# GPIOPins.net
KiCad netlist of a schematic drawn in Altium Designer
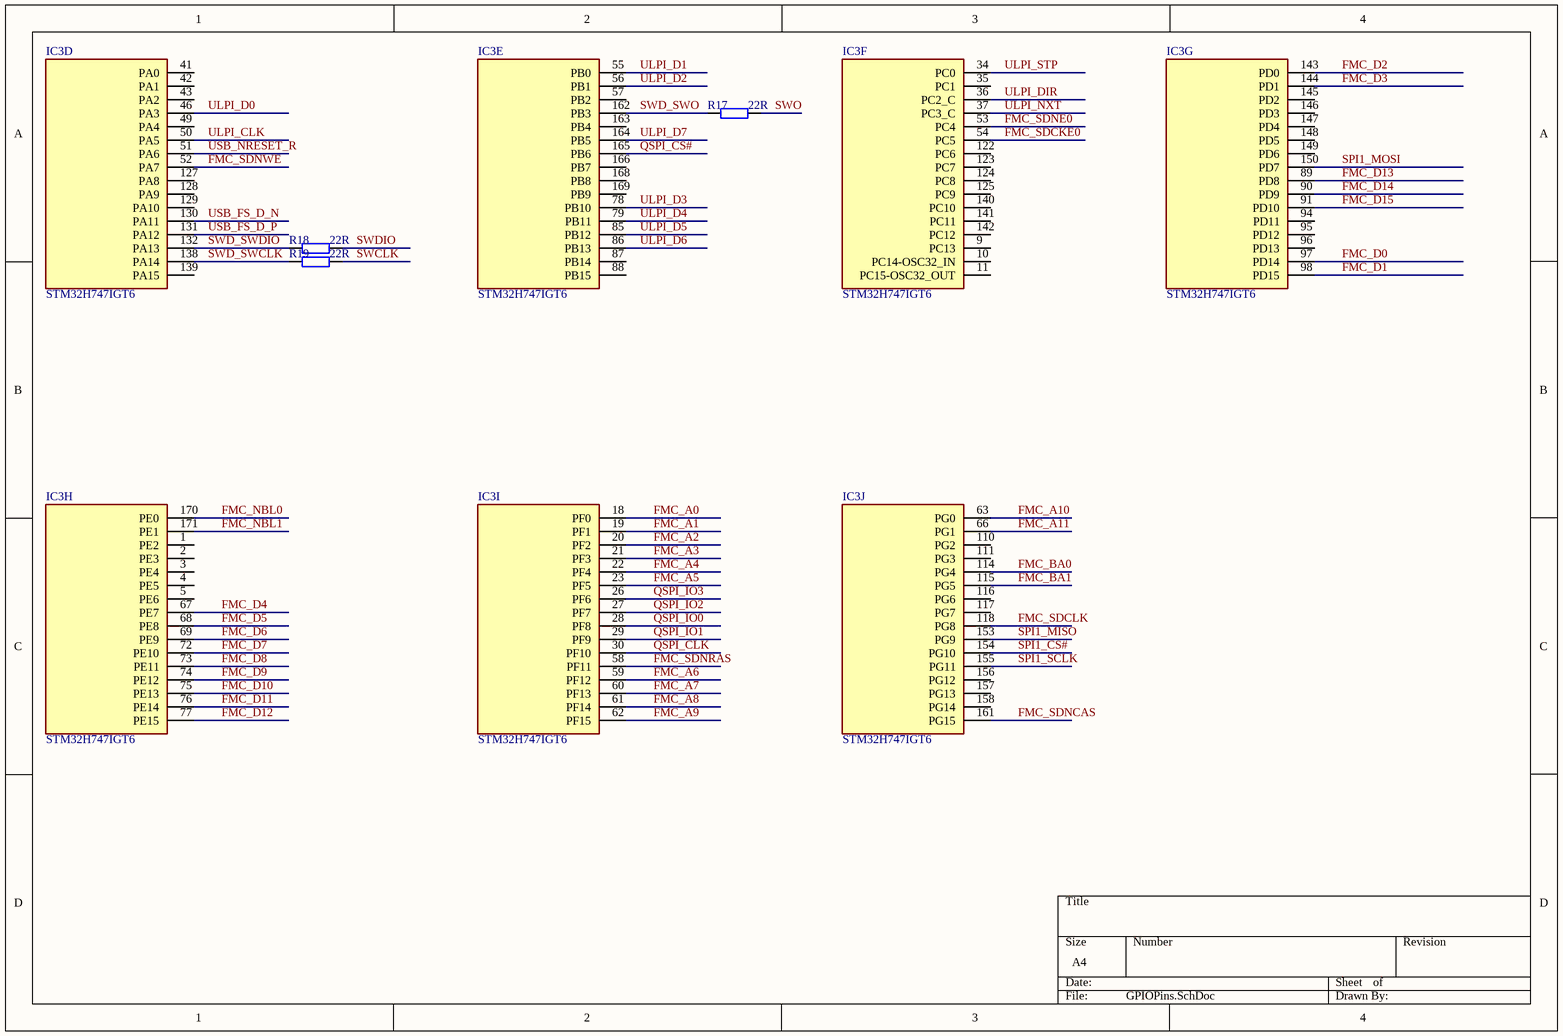
[diagram p0: GPIOPins.SchDoc]

(export (version "E")
  (design (tool "Eeschema 10.0.6"))
  (components
    (comp (ref "IC3")
      (value "STM32H747IGT6")
      (footprint "Footprint-Lib-PhilsLab:QFP50P2600X2600X160-176N")
      (description "Integrated Circuit")
      (fields (field (name "MOUSER PART NUMBER") "511-STM32H747IGT6"))
      (libsource (lib "Schematic-Lib-PhilsLab") (part "STM32H747IGT6"))
    )
    (comp (ref "R17")
      (value "22R")
      (footprint "RES_0402")
      (description "Resistor SMD 0402")
      (libsource (lib "Schematic-Lib-PhilsLab") (part "RES_0402"))
    )
    (comp (ref "R18")
      (value "22R")
      (footprint "RES_0402")
      (description "Resistor SMD 0402")
      (libsource (lib "Schematic-Lib-PhilsLab") (part "RES_0402"))
    )
    (comp (ref "R19")
      (value "22R")
      (footprint "RES_0402")
      (description "Resistor SMD 0402")
      (libsource (lib "Schematic-Lib-PhilsLab") (part "RES_0402"))
    )
  )
  (nets
    (net (code "1") (name "/FMC_A0") (class "Default")
      (node (ref "IC3") (pin "18") (pinfunction "PF0_18") (pintype "passive"))
    )
    (net (code "2") (name "/FMC_A1") (class "Default")
      (node (ref "IC3") (pin "19") (pinfunction "PF1_19") (pintype "passive"))
    )
    (net (code "3") (name "/FMC_A2") (class "Default")
      (node (ref "IC3") (pin "20") (pinfunction "PF2_20") (pintype "passive"))
    )
    (net (code "4") (name "/FMC_A3") (class "Default")
      (node (ref "IC3") (pin "21") (pinfunction "PF3_21") (pintype "passive"))
    )
    (net (code "5") (name "/FMC_A4") (class "Default")
      (node (ref "IC3") (pin "22") (pinfunction "PF4_22") (pintype "passive"))
    )
    (net (code "6") (name "/FMC_A5") (class "Default")
      (node (ref "IC3") (pin "23") (pinfunction "PF5_23") (pintype "passive"))
    )
    (net (code "7") (name "/FMC_A6") (class "Default")
      (node (ref "IC3") (pin "59") (pinfunction "PF12_59") (pintype "passive"))
    )
    (net (code "8") (name "/FMC_A7") (class "Default")
      (node (ref "IC3") (pin "60") (pinfunction "PF13_60") (pintype "passive"))
    )
    (net (code "9") (name "/FMC_A8") (class "Default")
      (node (ref "IC3") (pin "61") (pinfunction "PF14_61") (pintype "passive"))
    )
    (net (code "10") (name "/FMC_A9") (class "Default")
      (node (ref "IC3") (pin "62") (pinfunction "PF15_62") (pintype "passive"))
    )
    (net (code "11") (name "/FMC_A10") (class "Default")
      (node (ref "IC3") (pin "63") (pinfunction "PG0_63") (pintype "passive"))
    )
    (net (code "12") (name "/FMC_A11") (class "Default")
      (node (ref "IC3") (pin "66") (pinfunction "PG1_66") (pintype "passive"))
    )
    (net (code "13") (name "/FMC_BA0") (class "Default")
      (node (ref "IC3") (pin "114") (pinfunction "PG4_114") (pintype "passive"))
    )
    (net (code "14") (name "/FMC_BA1") (class "Default")
      (node (ref "IC3") (pin "115") (pinfunction "PG5_115") (pintype "passive"))
    )
    (net (code "15") (name "/FMC_D0") (class "Default")
      (node (ref "IC3") (pin "97") (pinfunction "PD14_97") (pintype "passive"))
    )
    (net (code "16") (name "/FMC_D1") (class "Default")
      (node (ref "IC3") (pin "98") (pinfunction "PD15_98") (pintype "passive"))
    )
    (net (code "17") (name "/FMC_D2") (class "Default")
      (node (ref "IC3") (pin "143") (pinfunction "PD0_143") (pintype "passive"))
    )
    (net (code "18") (name "/FMC_D3") (class "Default")
      (node (ref "IC3") (pin "144") (pinfunction "PD1_144") (pintype "passive"))
    )
    (net (code "19") (name "/FMC_D4") (class "Default")
      (node (ref "IC3") (pin "67") (pinfunction "PE7_67") (pintype "passive"))
    )
    (net (code "20") (name "/FMC_D5") (class "Default")
      (node (ref "IC3") (pin "68") (pinfunction "PE8_68") (pintype "passive"))
    )
    (net (code "21") (name "/FMC_D6") (class "Default")
      (node (ref "IC3") (pin "69") (pinfunction "PE9_69") (pintype "passive"))
    )
    (net (code "22") (name "/FMC_D7") (class "Default")
      (node (ref "IC3") (pin "72") (pinfunction "PE10_72") (pintype "passive"))
    )
    (net (code "23") (name "/FMC_D8") (class "Default")
      (node (ref "IC3") (pin "73") (pinfunction "PE11_73") (pintype "passive"))
    )
    (net (code "24") (name "/FMC_D9") (class "Default")
      (node (ref "IC3") (pin "74") (pinfunction "PE12_74") (pintype "passive"))
    )
    (net (code "25") (name "/FMC_D10") (class "Default")
      (node (ref "IC3") (pin "75") (pinfunction "PE13_75") (pintype "passive"))
    )
    (net (code "26") (name "/FMC_D11") (class "Default")
      (node (ref "IC3") (pin "76") (pinfunction "PE14_76") (pintype "passive"))
    )
    (net (code "27") (name "/FMC_D12") (class "Default")
      (node (ref "IC3") (pin "77") (pinfunction "PE15_77") (pintype "passive"))
    )
    (net (code "28") (name "/FMC_D13") (class "Default")
      (node (ref "IC3") (pin "89") (pinfunction "PD8_89") (pintype "passive"))
    )
    (net (code "29") (name "/FMC_D14") (class "Default")
      (node (ref "IC3") (pin "90") (pinfunction "PD9_90") (pintype "passive"))
    )
    (net (code "30") (name "/FMC_D15") (class "Default")
      (node (ref "IC3") (pin "91") (pinfunction "PD10_91") (pintype "passive"))
    )
    (net (code "31") (name "/FMC_NBL0") (class "Default")
      (node (ref "IC3") (pin "170") (pinfunction "PE0_170") (pintype "passive"))
    )
    (net (code "32") (name "/FMC_NBL1") (class "Default")
      (node (ref "IC3") (pin "171") (pinfunction "PE1_171") (pintype "passive"))
    )
    (net (code "33") (name "/FMC_SDCKE0") (class "Default")
      (node (ref "IC3") (pin "54") (pinfunction "PC5_54") (pintype "passive"))
    )
    (net (code "34") (name "/FMC_SDCLK") (class "Default")
      (node (ref "IC3") (pin "118") (pinfunction "PG8_118") (pintype "passive"))
    )
    (net (code "35") (name "/FMC_SDNCAS") (class "Default")
      (node (ref "IC3") (pin "161") (pinfunction "PG15_161") (pintype "passive"))
    )
    (net (code "36") (name "/FMC_SDNE0") (class "Default")
      (node (ref "IC3") (pin "53") (pinfunction "PC4_53") (pintype "passive"))
    )
    (net (code "37") (name "/FMC_SDNRAS") (class "Default")
      (node (ref "IC3") (pin "58") (pinfunction "PF11_58") (pintype "passive"))
    )
    (net (code "38") (name "/FMC_SDNWE") (class "Default")
      (node (ref "IC3") (pin "52") (pinfunction "PA7_52") (pintype "passive"))
    )
    (net (code "39") (name "/QSPI_CLK") (class "Default")
      (node (ref "IC3") (pin "30") (pinfunction "PF10_30") (pintype "passive"))
    )
    (net (code "40") (name "/QSPI_CS#") (class "Default")
      (node (ref "IC3") (pin "165") (pinfunction "PB6_165") (pintype "passive"))
    )
    (net (code "41") (name "/QSPI_IO0") (class "Default")
      (node (ref "IC3") (pin "28") (pinfunction "PF8_28") (pintype "passive"))
    )
    (net (code "42") (name "/QSPI_IO1") (class "Default")
      (node (ref "IC3") (pin "29") (pinfunction "PF9_29") (pintype "passive"))
    )
    (net (code "43") (name "/QSPI_IO2") (class "Default")
      (node (ref "IC3") (pin "27") (pinfunction "PF7_27") (pintype "passive"))
    )
    (net (code "44") (name "/QSPI_IO3") (class "Default")
      (node (ref "IC3") (pin "26") (pinfunction "PF6_26") (pintype "passive"))
    )
    (net (code "45") (name "/SPI1_CS#") (class "Default")
      (node (ref "IC3") (pin "154") (pinfunction "PG10_154") (pintype "passive"))
    )
    (net (code "46") (name "/SPI1_MISO") (class "Default")
      (node (ref "IC3") (pin "153") (pinfunction "PG9_153") (pintype "passive"))
    )
    (net (code "47") (name "/SPI1_MOSI") (class "Default")
      (node (ref "IC3") (pin "150") (pinfunction "PD7_150") (pintype "passive"))
    )
    (net (code "48") (name "/SPI1_SCLK") (class "Default")
      (node (ref "IC3") (pin "155") (pinfunction "PG11_155") (pintype "passive"))
    )
    (net (code "49") (name "/SWCLK") (class "Default")
      (node (ref "R19") (pin "1") (pinfunction "1_1") (pintype "passive"))
    )
    (net (code "50") (name "/SWDIO") (class "Default")
      (node (ref "R18") (pin "1") (pinfunction "1_1") (pintype "passive"))
    )
    (net (code "51") (name "/SWD_SWCLK") (class "Default")
      (node (ref "IC3") (pin "138") (pinfunction "PA14_138") (pintype "passive"))
      (node (ref "R19") (pin "2") (pinfunction "2_2") (pintype "passive"))
    )
    (net (code "52") (name "/SWD_SWDIO") (class "Default")
      (node (ref "IC3") (pin "132") (pinfunction "PA13_132") (pintype "passive"))
      (node (ref "R18") (pin "2") (pinfunction "2_2") (pintype "passive"))
    )
    (net (code "53") (name "/SWD_SWO") (class "Default")
      (node (ref "IC3") (pin "162") (pinfunction "PB3_162") (pintype "passive"))
      (node (ref "R17") (pin "2") (pinfunction "2_2") (pintype "passive"))
    )
    (net (code "54") (name "/SWO") (class "Default")
      (node (ref "R17") (pin "1") (pinfunction "1_1") (pintype "passive"))
    )
    (net (code "55") (name "/ULPI_CLK") (class "Default")
      (node (ref "IC3") (pin "50") (pinfunction "PA5_50") (pintype "passive"))
    )
    (net (code "56") (name "/ULPI_D0") (class "Default")
      (node (ref "IC3") (pin "46") (pinfunction "PA3_46") (pintype "passive"))
    )
    (net (code "57") (name "/ULPI_D1") (class "Default")
      (node (ref "IC3") (pin "55") (pinfunction "PB0_55") (pintype "passive"))
    )
    (net (code "58") (name "/ULPI_D2") (class "Default")
      (node (ref "IC3") (pin "56") (pinfunction "PB1_56") (pintype "passive"))
    )
    (net (code "59") (name "/ULPI_D3") (class "Default")
      (node (ref "IC3") (pin "78") (pinfunction "PB10_78") (pintype "passive"))
    )
    (net (code "60") (name "/ULPI_D4") (class "Default")
      (node (ref "IC3") (pin "79") (pinfunction "PB11_79") (pintype "passive"))
    )
    (net (code "61") (name "/ULPI_D5") (class "Default")
      (node (ref "IC3") (pin "85") (pinfunction "PB12_85") (pintype "passive"))
    )
    (net (code "62") (name "/ULPI_D6") (class "Default")
      (node (ref "IC3") (pin "86") (pinfunction "PB13_86") (pintype "passive"))
    )
    (net (code "63") (name "/ULPI_D7") (class "Default")
      (node (ref "IC3") (pin "164") (pinfunction "PB5_164") (pintype "passive"))
    )
    (net (code "64") (name "/ULPI_DIR") (class "Default")
      (node (ref "IC3") (pin "36") (pinfunction "PC2_C_36") (pintype "passive"))
    )
    (net (code "65") (name "/ULPI_NXT") (class "Default")
      (node (ref "IC3") (pin "37") (pinfunction "PC3_C_37") (pintype "passive"))
    )
    (net (code "66") (name "/ULPI_STP") (class "Default")
      (node (ref "IC3") (pin "34") (pinfunction "PC0_34") (pintype "passive"))
    )
    (net (code "67") (name "/USB_FS_D_N") (class "Default")
      (node (ref "IC3") (pin "130") (pinfunction "PA11_130") (pintype "passive"))
    )
    (net (code "68") (name "/USB_FS_D_P") (class "Default")
      (node (ref "IC3") (pin "131") (pinfunction "PA12_131") (pintype "passive"))
    )
    (net (code "69") (name "/USB_NRESET_R") (class "Default")
      (node (ref "IC3") (pin "51") (pinfunction "PA6_51") (pintype "passive"))
    )
    (net (code "70") (name "unconnected-(IC3D-PA0-Pad41)") (class "Default")
      (node (ref "IC3") (pin "41") (pinfunction "PA0_41") (pintype "passive"))
    )
    (net (code "71") (name "unconnected-(IC3D-PA1-Pad42)") (class "Default")
      (node (ref "IC3") (pin "42") (pinfunction "PA1_42") (pintype "passive"))
    )
    (net (code "72") (name "unconnected-(IC3D-PA2-Pad43)") (class "Default")
      (node (ref "IC3") (pin "43") (pinfunction "PA2_43") (pintype "passive"))
    )
    (net (code "73") (name "unconnected-(IC3D-PA4-Pad49)") (class "Default")
      (node (ref "IC3") (pin "49") (pinfunction "PA4_49") (pintype "passive"))
    )
    (net (code "74") (name "unconnected-(IC3D-PA8-Pad127)") (class "Default")
      (node (ref "IC3") (pin "127") (pinfunction "PA8_127") (pintype "passive"))
    )
    (net (code "75") (name "unconnected-(IC3D-PA9-Pad128)") (class "Default")
      (node (ref "IC3") (pin "128") (pinfunction "PA9_128") (pintype "passive"))
    )
    (net (code "76") (name "unconnected-(IC3D-PA10-Pad129)") (class "Default")
      (node (ref "IC3") (pin "129") (pinfunction "PA10_129") (pintype "passive"))
    )
    (net (code "77") (name "unconnected-(IC3D-PA15-Pad139)") (class "Default")
      (node (ref "IC3") (pin "139") (pinfunction "PA15_139") (pintype "passive"))
    )
    (net (code "78") (name "unconnected-(IC3E-PB2-Pad57)") (class "Default")
      (node (ref "IC3") (pin "57") (pinfunction "PB2_57") (pintype "passive"))
    )
    (net (code "79") (name "unconnected-(IC3E-PB4-Pad163)") (class "Default")
      (node (ref "IC3") (pin "163") (pinfunction "PB4_163") (pintype "passive"))
    )
    (net (code "80") (name "unconnected-(IC3E-PB7-Pad166)") (class "Default")
      (node (ref "IC3") (pin "166") (pinfunction "PB7_166") (pintype "passive"))
    )
    (net (code "81") (name "unconnected-(IC3E-PB8-Pad168)") (class "Default")
      (node (ref "IC3") (pin "168") (pinfunction "PB8_168") (pintype "passive"))
    )
    (net (code "82") (name "unconnected-(IC3E-PB9-Pad169)") (class "Default")
      (node (ref "IC3") (pin "169") (pinfunction "PB9_169") (pintype "passive"))
    )
    (net (code "83") (name "unconnected-(IC3E-PB14-Pad87)") (class "Default")
      (node (ref "IC3") (pin "87") (pinfunction "PB14_87") (pintype "passive"))
    )
    (net (code "84") (name "unconnected-(IC3E-PB15-Pad88)") (class "Default")
      (node (ref "IC3") (pin "88") (pinfunction "PB15_88") (pintype "passive"))
    )
    (net (code "85") (name "unconnected-(IC3F-PC1-Pad35)") (class "Default")
      (node (ref "IC3") (pin "35") (pinfunction "PC1_35") (pintype "passive"))
    )
    (net (code "86") (name "unconnected-(IC3F-PC6-Pad122)") (class "Default")
      (node (ref "IC3") (pin "122") (pinfunction "PC6_122") (pintype "passive"))
    )
    (net (code "87") (name "unconnected-(IC3F-PC7-Pad123)") (class "Default")
      (node (ref "IC3") (pin "123") (pinfunction "PC7_123") (pintype "passive"))
    )
    (net (code "88") (name "unconnected-(IC3F-PC8-Pad124)") (class "Default")
      (node (ref "IC3") (pin "124") (pinfunction "PC8_124") (pintype "passive"))
    )
    (net (code "89") (name "unconnected-(IC3F-PC9-Pad125)") (class "Default")
      (node (ref "IC3") (pin "125") (pinfunction "PC9_125") (pintype "passive"))
    )
    (net (code "90") (name "unconnected-(IC3F-PC10-Pad140)") (class "Default")
      (node (ref "IC3") (pin "140") (pinfunction "PC10_140") (pintype "passive"))
    )
    (net (code "91") (name "unconnected-(IC3F-PC11-Pad141)") (class "Default")
      (node (ref "IC3") (pin "141") (pinfunction "PC11_141") (pintype "passive"))
    )
    (net (code "92") (name "unconnected-(IC3F-PC12-Pad142)") (class "Default")
      (node (ref "IC3") (pin "142") (pinfunction "PC12_142") (pintype "passive"))
    )
    (net (code "93") (name "unconnected-(IC3F-PC13-Pad9)") (class "Default")
      (node (ref "IC3") (pin "9") (pinfunction "PC13_9") (pintype "passive"))
    )
    (net (code "94") (name "unconnected-(IC3F-PC14-OSC32_IN-Pad10)") (class "Default")
      (node (ref "IC3") (pin "10") (pinfunction "PC14-OSC32_IN_10") (pintype "passive"))
    )
    (net (code "95") (name "unconnected-(IC3F-PC15-OSC32_OUT-Pad11)") (class "Default")
      (node (ref "IC3") (pin "11") (pinfunction "PC15-OSC32_OUT_11") (pintype "passive"))
    )
    (net (code "96") (name "unconnected-(IC3G-PD2-Pad145)") (class "Default")
      (node (ref "IC3") (pin "145") (pinfunction "PD2_145") (pintype "passive"))
    )
    (net (code "97") (name "unconnected-(IC3G-PD3-Pad146)") (class "Default")
      (node (ref "IC3") (pin "146") (pinfunction "PD3_146") (pintype "passive"))
    )
    (net (code "98") (name "unconnected-(IC3G-PD4-Pad147)") (class "Default")
      (node (ref "IC3") (pin "147") (pinfunction "PD4_147") (pintype "passive"))
    )
    (net (code "99") (name "unconnected-(IC3G-PD5-Pad148)") (class "Default")
      (node (ref "IC3") (pin "148") (pinfunction "PD5_148") (pintype "passive"))
    )
    (net (code "100") (name "unconnected-(IC3G-PD6-Pad149)") (class "Default")
      (node (ref "IC3") (pin "149") (pinfunction "PD6_149") (pintype "passive"))
    )
    (net (code "101") (name "unconnected-(IC3G-PD11-Pad94)") (class "Default")
      (node (ref "IC3") (pin "94") (pinfunction "PD11_94") (pintype "passive"))
    )
    (net (code "102") (name "unconnected-(IC3G-PD12-Pad95)") (class "Default")
      (node (ref "IC3") (pin "95") (pinfunction "PD12_95") (pintype "passive"))
    )
    (net (code "103") (name "unconnected-(IC3G-PD13-Pad96)") (class "Default")
      (node (ref "IC3") (pin "96") (pinfunction "PD13_96") (pintype "passive"))
    )
    (net (code "104") (name "unconnected-(IC3H-PE2-Pad1)") (class "Default")
      (node (ref "IC3") (pin "1") (pinfunction "PE2_1") (pintype "passive"))
    )
    (net (code "105") (name "unconnected-(IC3H-PE3-Pad2)") (class "Default")
      (node (ref "IC3") (pin "2") (pinfunction "PE3_2") (pintype "passive"))
    )
    (net (code "106") (name "unconnected-(IC3H-PE4-Pad3)") (class "Default")
      (node (ref "IC3") (pin "3") (pinfunction "PE4_3") (pintype "passive"))
    )
    (net (code "107") (name "unconnected-(IC3H-PE5-Pad4)") (class "Default")
      (node (ref "IC3") (pin "4") (pinfunction "PE5_4") (pintype "passive"))
    )
    (net (code "108") (name "unconnected-(IC3H-PE6-Pad5)") (class "Default")
      (node (ref "IC3") (pin "5") (pinfunction "PE6_5") (pintype "passive"))
    )
    (net (code "109") (name "unconnected-(IC3J-PG2-Pad110)") (class "Default")
      (node (ref "IC3") (pin "110") (pinfunction "PG2_110") (pintype "passive"))
    )
    (net (code "110") (name "unconnected-(IC3J-PG3-Pad111)") (class "Default")
      (node (ref "IC3") (pin "111") (pinfunction "PG3_111") (pintype "passive"))
    )
    (net (code "111") (name "unconnected-(IC3J-PG6-Pad116)") (class "Default")
      (node (ref "IC3") (pin "116") (pinfunction "PG6_116") (pintype "passive"))
    )
    (net (code "112") (name "unconnected-(IC3J-PG7-Pad117)") (class "Default")
      (node (ref "IC3") (pin "117") (pinfunction "PG7_117") (pintype "passive"))
    )
    (net (code "113") (name "unconnected-(IC3J-PG12-Pad156)") (class "Default")
      (node (ref "IC3") (pin "156") (pinfunction "PG12_156") (pintype "passive"))
    )
    (net (code "114") (name "unconnected-(IC3J-PG13-Pad157)") (class "Default")
      (node (ref "IC3") (pin "157") (pinfunction "PG13_157") (pintype "passive"))
    )
    (net (code "115") (name "unconnected-(IC3J-PG14-Pad158)") (class "Default")
      (node (ref "IC3") (pin "158") (pinfunction "PG14_158") (pintype "passive"))
    )
  )
)
